# AWG_EEM_Connectors_JTAG.net
KiCad netlist of a schematic drawn in Altium Designer
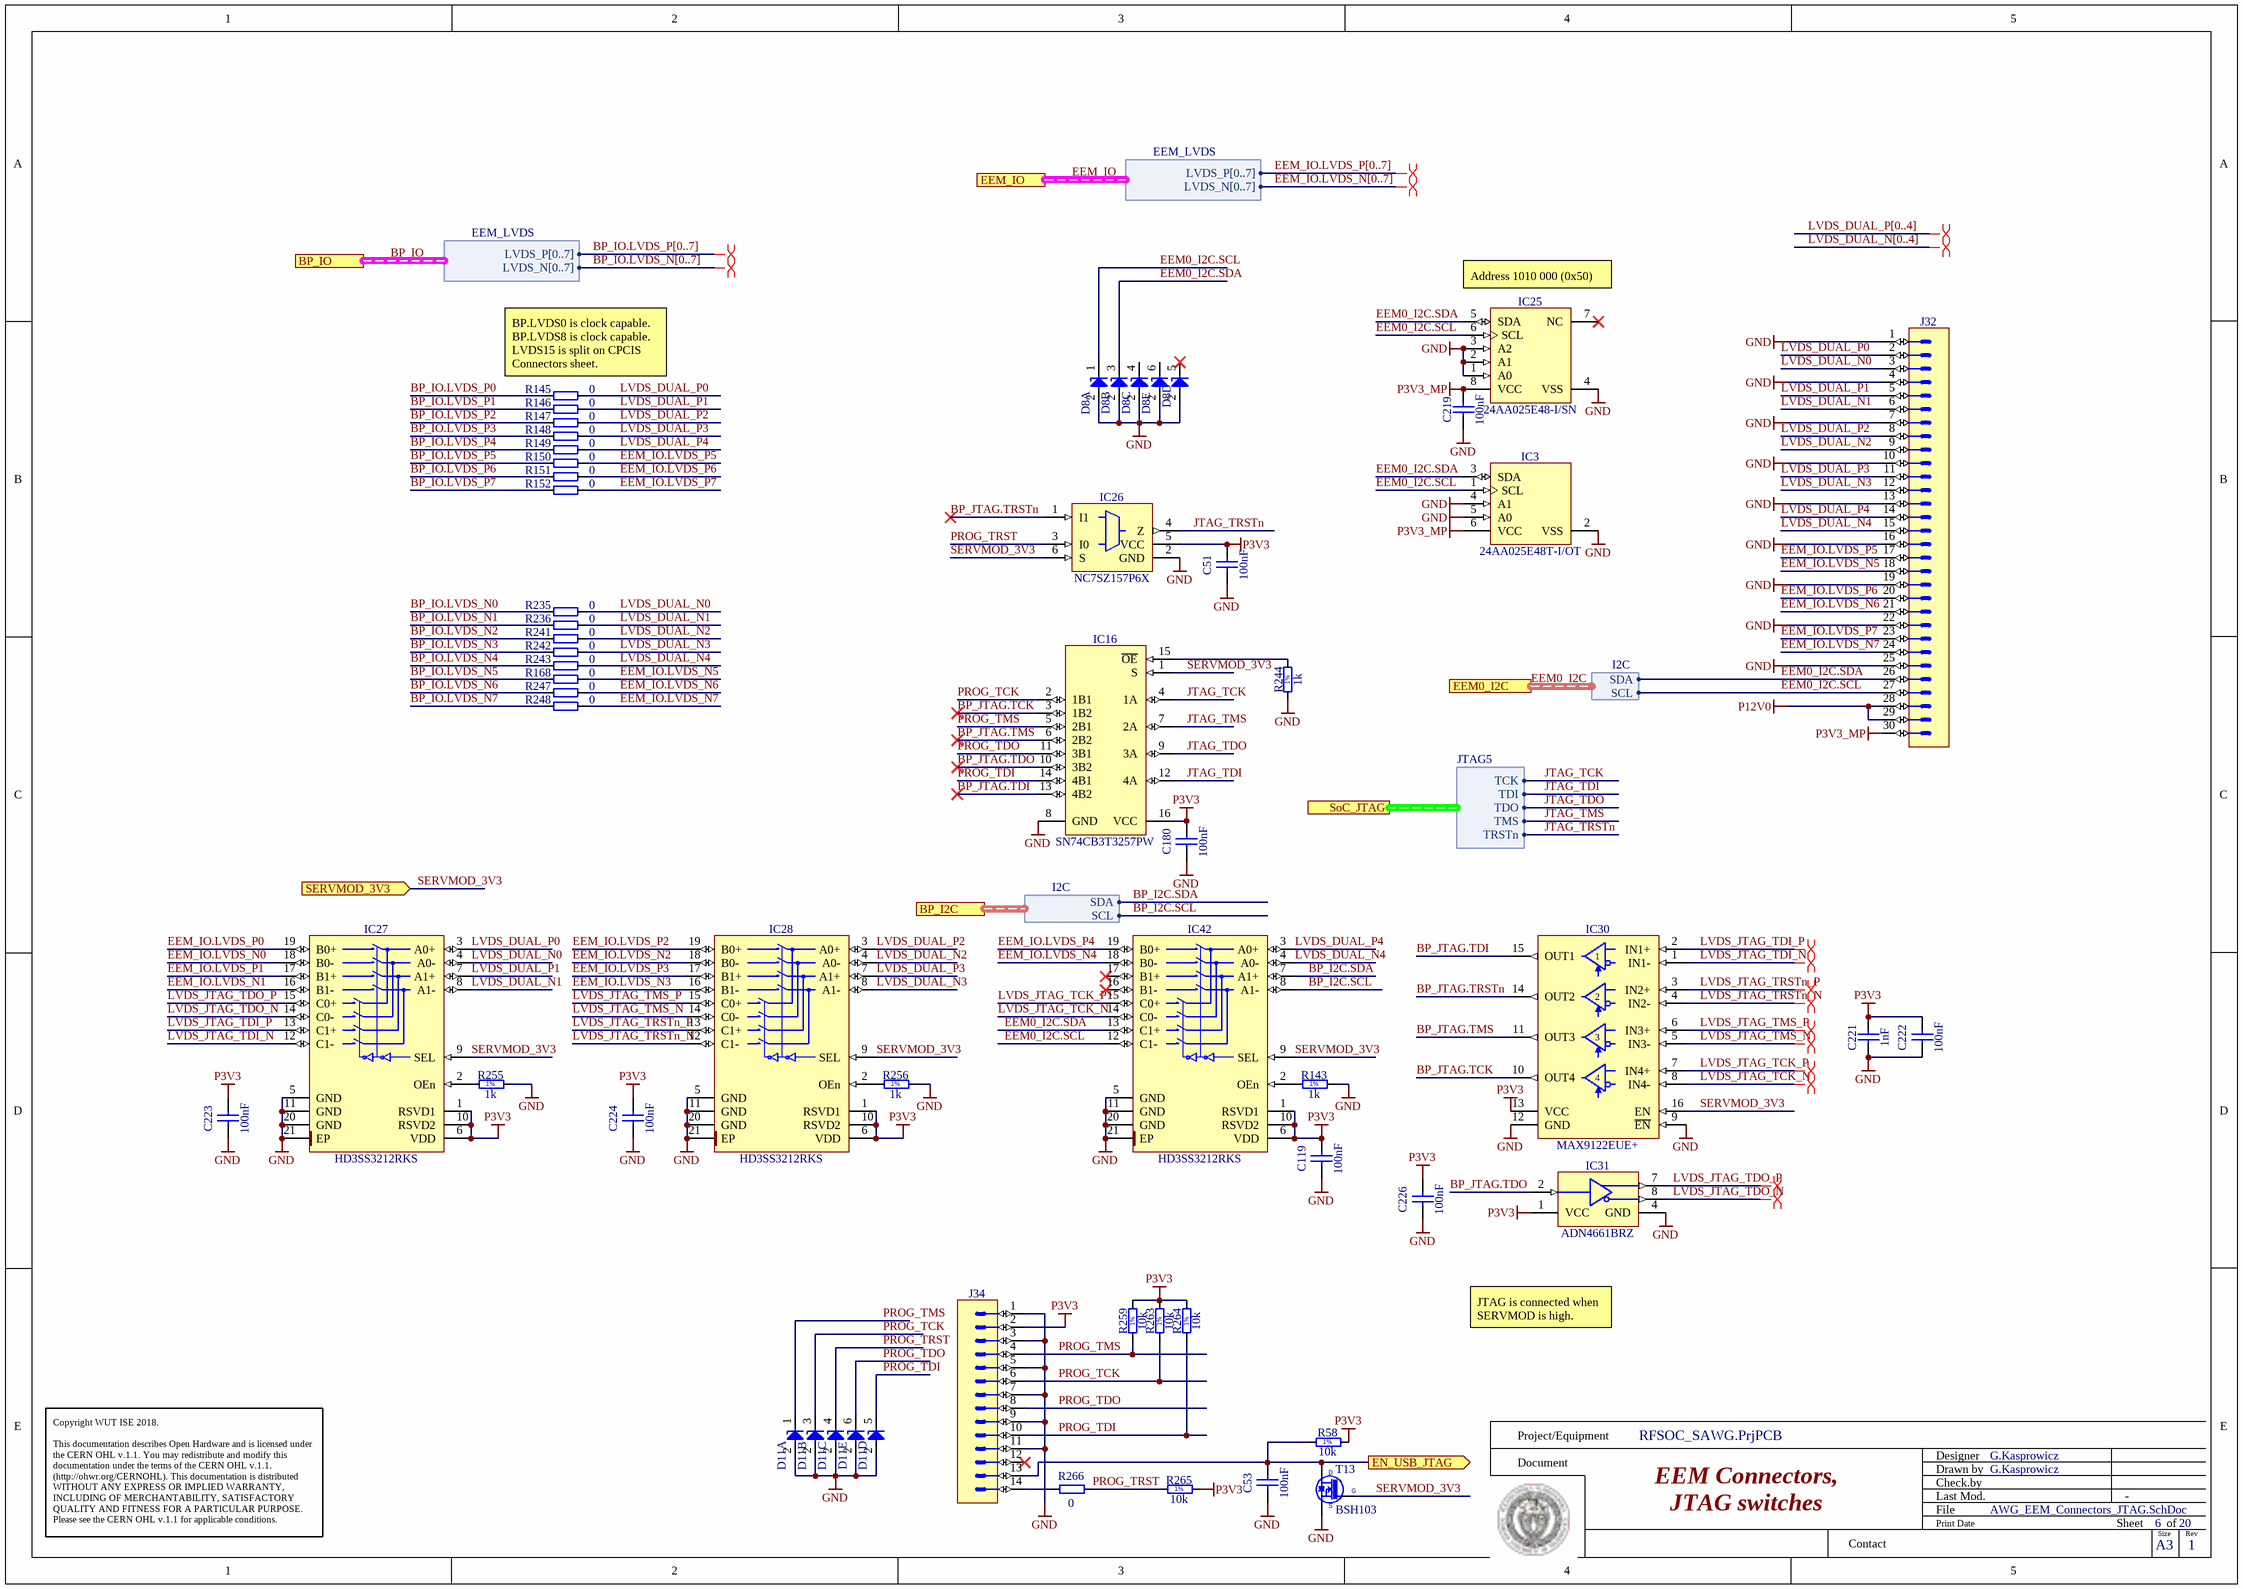
[diagram p0: AWG_EEM_Connectors_JTAG.SchDoc]

(export (version "E")
  (design (tool "Eeschema 10.0.6"))
  (components
    (comp (ref "C51")
      (value "100nF")
      (footprint "CAPC1005X55N")
      (description "Non-polarised capacitor")
      (fields
        (field (name "PART NUMBER") "CC0402_100NF_25V_10%_X7R_YUDEN_TMK105B7104KVHF")
        (field (name "VOLTAGE") "25V")
        (field (name "AUTHOR") "CERN DEM JLC")
      )
      (libsource (lib "Capacitors") (part "Capacitor - non polarized"))
    )
    (comp (ref "C53")
      (value "100nF")
      (footprint "CAPC1005X55N")
      (description "Non-polarised capacitor")
      (fields
        (field (name "PART NUMBER") "CC0402_100NF_25V_10%_X7R_YUDEN_TMK105B7104KVHF")
        (field (name "VOLTAGE") "25V")
        (field (name "AUTHOR") "CERN DEM JLC")
      )
      (libsource (lib "Capacitors") (part "Capacitor - non polarized"))
    )
    (comp (ref "C119")
      (value "100nF")
      (footprint "CAPC1005X55N")
      (description "Non-polarised capacitor")
      (fields
        (field (name "PART NUMBER") "CC0402_100NF_25V_10%_X7R_YUDEN_TMK105B7104KVHF")
        (field (name "VOLTAGE") "25V")
        (field (name "AUTHOR") "CERN DEM JLC")
      )
      (libsource (lib "Capacitors") (part "Capacitor - non polarized"))
    )
    (comp (ref "C180")
      (value "100nF")
      (footprint "CAPC1005X55N")
      (description "Non-polarised capacitor")
      (fields
        (field (name "PART NUMBER") "CC0402_100NF_25V_10%_X7R_YUDEN_TMK105B7104KVHF")
        (field (name "VOLTAGE") "25V")
        (field (name "AUTHOR") "CERN DEM JLC")
      )
      (libsource (lib "Capacitors") (part "Capacitor - non polarized"))
    )
    (comp (ref "C219")
      (value "100nF")
      (footprint "CAPC1005X55N")
      (description "Non-polarised capacitor")
      (fields
        (field (name "PART NUMBER") "CC0402_100NF_25V_10%_X7R_YUDEN_TMK105B7104KVHF")
        (field (name "VOLTAGE") "25V")
        (field (name "AUTHOR") "CERN DEM JLC")
      )
      (libsource (lib "Capacitors") (part "Capacitor - non polarized"))
    )
    (comp (ref "C221")
      (value "1nF")
      (footprint "CAPC1005X55N")
      (description "Non-polarised capacitor")
      (fields
        (field (name "MANUFACTURER PART NUMBER") "CC0402_1NF_50V_10%_X7R")
        (field (name "MANUFACTURER") "GENERIC")
        (field (name "AUTHOR") "CERN DEM JLC")
      )
      (libsource (lib "Capacitors") (part "Capacitor - non polarized"))
    )
    (comp (ref "C222")
      (value "100nF")
      (footprint "CAPC1005X55N")
      (description "Non-polarised capacitor")
      (fields
        (field (name "PART NUMBER") "CC0402_100NF_25V_10%_X7R_YUDEN_TMK105B7104KVHF")
        (field (name "VOLTAGE") "25V")
        (field (name "AUTHOR") "CERN DEM JLC")
      )
      (libsource (lib "Capacitors") (part "Capacitor - non polarized"))
    )
    (comp (ref "C223")
      (value "100nF")
      (footprint "CAPC1005X55N")
      (description "Non-polarised capacitor")
      (fields
        (field (name "PART NUMBER") "CC0402_100NF_25V_10%_X7R_YUDEN_TMK105B7104KVHF")
        (field (name "VOLTAGE") "25V")
        (field (name "AUTHOR") "CERN DEM JLC")
      )
      (libsource (lib "Capacitors") (part "Capacitor - non polarized"))
    )
    (comp (ref "C224")
      (value "100nF")
      (footprint "CAPC1005X55N")
      (description "Non-polarised capacitor")
      (fields
        (field (name "PART NUMBER") "CC0402_100NF_25V_10%_X7R_YUDEN_TMK105B7104KVHF")
        (field (name "VOLTAGE") "25V")
        (field (name "AUTHOR") "CERN DEM JLC")
      )
      (libsource (lib "Capacitors") (part "Capacitor - non polarized"))
    )
    (comp (ref "C226")
      (value "100nF")
      (footprint "CAPC1005X55N")
      (description "Non-polarised capacitor")
      (fields
        (field (name "PART NUMBER") "CC0402_100NF_25V_10%_X7R_YUDEN_TMK105B7104KVHF")
        (field (name "VOLTAGE") "25V")
        (field (name "AUTHOR") "CERN DEM JLC")
      )
      (libsource (lib "Capacitors") (part "Capacitor - non polarized"))
    )
    (comp (ref "D8")
      (value "PESD3V3L5UY")
      (footprint "SOT65P210X110-6N")
      (description "Fivefold ESD Protection Diode Arrays")
      (fields
        (field (name "VOLTAGE") "3.3V")
        (field (name "POWER") "200W")
        (field (name "AUTHOR") "CERN DEM WB")
      )
      (libsource (lib "ICs And Semiconductors") (part "PESD Array 5diodes 6pins Common anode2"))
    )
    (comp (ref "D11")
      (value "PESD3V3L5UY")
      (footprint "SOT65P210X110-6N")
      (description "Fivefold ESD Protection Diode Arrays")
      (fields
        (field (name "VOLTAGE") "3.3V")
        (field (name "POWER") "200W")
        (field (name "AUTHOR") "CERN DEM WB")
      )
      (libsource (lib "ICs And Semiconductors") (part "PESD Array 5diodes 6pins Common anode2"))
    )
    (comp (ref "IC3")
      (value "24AA025E48T-I/OT")
      (footprint "SOT95P280X145-6N")
      (description "1.7V-5.5V, 2K I2C Serial EEPROM With EUI-48 Node Identity")
      (fields (field (name "MANUFACTURER") "MICROCHIP TECHNOLOGY") (field (name "AUTHOR") "CERN DEM BC"))
      (libsource (lib "ICs And Semiconductors") (part "24AA025E48T-I/OT"))
    )
    (comp (ref "IC16")
      (value "SN74CB3T3257PW")
      (footprint "SOP65P640X120-16N")
      (description "4-BIT 1-OF-2 FET Multiplexer/Demultiplexer 2.5V/3.3V Low-Voltage Bus Switch 5V Tolerant Shifter")
      (fields (field (name "MANUFACTURER") "TEXAS INSTRUMENTS") (field (name "AUTHOR") "CERN DEM JLC"))
      (libsource (lib "ICs And Semiconductors") (part "743257"))
    )
    (comp (ref "IC25")
      (value "24AA025E48-I/SN")
      (footprint "SOIC127P600X175-8N")
      (description "1.7V-5.5V, 2K I2C™ Serial EEPROMs with EUI-48™ Node Identity")
      (fields (field (name "MANUFACTURER") "MICROCHIP TECHNOLOGY") (field (name "AUTHOR") "CERN DEM MR"))
      (libsource (lib "ICs And Semiconductors") (part "24AA025E48-I/SN"))
    )
    (comp (ref "IC26")
      (value "NC7SZ157P6X")
      (footprint "SOT65P210X110-6N")
      (description "TinyLogic® UHS 2-Input Non-Inverting Multiplexer")
      (fields (field (name "MANUFACTURER") "FAIRCHILD SEMICONDUCTOR") (field (name "AUTHOR") "CERN DEM JLC"))
      (libsource (lib "ICs And Semiconductors") (part "NC7SZ157"))
    )
    (comp (ref "IC27")
      (value "HD3SS3212RKS")
      (footprint "TEXAS_RKS0020A")
      (description "Two-Channel Differential 2:1/1:2 USB3.1 Mux/Demux")
      (fields (field (name "MANUFACTURER") "TEXAS INSTRUMENTS") (field (name "AUTHOR") "CERN DEM BC"))
      (libsource (lib "ICs And Semiconductors") (part "HD3SS3212RKS"))
    )
    (comp (ref "IC28")
      (value "HD3SS3212RKS")
      (footprint "TEXAS_RKS0020A")
      (description "Two-Channel Differential 2:1/1:2 USB3.1 Mux/Demux")
      (fields (field (name "MANUFACTURER") "TEXAS INSTRUMENTS") (field (name "AUTHOR") "CERN DEM BC"))
      (libsource (lib "ICs And Semiconductors") (part "HD3SS3212RKS"))
    )
    (comp (ref "IC30")
      (value "MAX9122EUE+")
      (footprint "SOP65P640X110-16N")
      (description "Quad LVDS Line Receivers with Integrated Termination and Flow-Through Pinout")
      (fields (field (name "MANUFACTURER") "MAXIM") (field (name "AUTHOR") "CERN DEM MR"))
      (libsource (lib "ICs And Semiconductors") (part "MAX9122"))
    )
    (comp (ref "IC31")
      (value "ADN4661BRZ")
      (footprint "SOIC127P600X175-8N")
      (description "Single, 3V, CMOS, LVDS, High Speed Differential Driver")
      (fields (field (name "MANUFACTURER") "ANALOG DEVICES") (field (name "AUTHOR") "CERN DEM JMW"))
      (libsource (lib "ICs And Semiconductors") (part "ADN4661"))
    )
    (comp (ref "IC42")
      (value "HD3SS3212RKS")
      (footprint "TEXAS_RKS0020A")
      (description "Two-Channel Differential 2:1/1:2 USB3.1 Mux/Demux")
      (fields (field (name "MANUFACTURER") "TEXAS INSTRUMENTS") (field (name "AUTHOR") "CERN DEM BC"))
      (libsource (lib "ICs And Semiconductors") (part "HD3SS3212RKS"))
    )
    (comp (ref "J32")
      (value "~")
      (footprint "3M_N2530-6002RB")
      (description "Connector 30 Male")
      (fields
        (field (name "PART NUMBER") "3M_N2530-6002RB")
        (field (name "MANUFACTURER") "3M")
        (field (name "AUTHOR") "CERN DEM JLC")
      )
      (libsource (lib "Connectors") (part "Connector 30 Male"))
    )
    (comp (ref "J34")
      (value "Milli-Grid™")
      (footprint "MOLEX_87832-1420")
      (description "Connector 14 Male")
      (fields
        (field (name "PART NUMBER") "MOLEX_87832-1420")
        (field (name "MANUFACTURER") "MOLEX")
        (field (name "AUTHOR") "CERN DEM JLC")
      )
      (libsource (lib "Connectors") (part "Connector 14 Male"))
    )
    (comp (ref "R58")
      (value "10k")
      (footprint "RESC1005X40N")
      (description "Resistor - 1%")
      (fields
        (field (name "PART NUMBER") "R0402_10K_1%_0.0625W_100PPM")
        (field (name "POWER") "0.0625W")
        (field (name "AUTHOR") "CERN DEM JLC")
      )
      (libsource (lib "Resistors") (part "Resistor - 1%"))
    )
    (comp (ref "R143")
      (value "1k")
      (footprint "RESC1005X40N")
      (description "Resistor - 1%")
      (fields
        (field (name "PART NUMBER") "R0402_1K_1%_0.0625W_100PPM")
        (field (name "POWER") "0.0625W")
        (field (name "AUTHOR") "CERN DEM JLC")
      )
      (libsource (lib "Resistors") (part "Resistor - 1%"))
    )
    (comp (ref "R145")
      (value "0")
      (footprint "RESC1005X40N")
      (description "Resistor")
      (fields
        (field (name "PART NUMBER") "R0402_0R_JUMPER")
        (field (name "MANUFACTURER") "GENERIC")
        (field (name "AUTHOR") "CERN DEM JLC")
      )
      (libsource (lib "Resistors") (part "Resistor"))
    )
    (comp (ref "R146")
      (value "0")
      (footprint "RESC1005X40N")
      (description "Resistor")
      (fields
        (field (name "PART NUMBER") "R0402_0R_JUMPER")
        (field (name "MANUFACTURER") "GENERIC")
        (field (name "AUTHOR") "CERN DEM JLC")
      )
      (libsource (lib "Resistors") (part "Resistor"))
    )
    (comp (ref "R147")
      (value "0")
      (footprint "RESC1005X40N")
      (description "Resistor")
      (fields
        (field (name "PART NUMBER") "R0402_0R_JUMPER")
        (field (name "MANUFACTURER") "GENERIC")
        (field (name "AUTHOR") "CERN DEM JLC")
      )
      (libsource (lib "Resistors") (part "Resistor"))
    )
    (comp (ref "R148")
      (value "0")
      (footprint "RESC1005X40N")
      (description "Resistor")
      (fields
        (field (name "PART NUMBER") "R0402_0R_JUMPER")
        (field (name "MANUFACTURER") "GENERIC")
        (field (name "AUTHOR") "CERN DEM JLC")
      )
      (libsource (lib "Resistors") (part "Resistor"))
    )
    (comp (ref "R149")
      (value "0")
      (footprint "RESC1005X40N")
      (description "Resistor")
      (fields
        (field (name "PART NUMBER") "R0402_0R_JUMPER")
        (field (name "MANUFACTURER") "GENERIC")
        (field (name "AUTHOR") "CERN DEM JLC")
      )
      (libsource (lib "Resistors") (part "Resistor"))
    )
    (comp (ref "R150")
      (value "0")
      (footprint "RESC1005X40N")
      (description "Resistor")
      (fields
        (field (name "PART NUMBER") "R0402_0R_JUMPER")
        (field (name "MANUFACTURER") "GENERIC")
        (field (name "AUTHOR") "CERN DEM JLC")
      )
      (libsource (lib "Resistors") (part "Resistor"))
    )
    (comp (ref "R151")
      (value "0")
      (footprint "RESC1005X40N")
      (description "Resistor")
      (fields
        (field (name "PART NUMBER") "R0402_0R_JUMPER")
        (field (name "MANUFACTURER") "GENERIC")
        (field (name "AUTHOR") "CERN DEM JLC")
      )
      (libsource (lib "Resistors") (part "Resistor"))
    )
    (comp (ref "R152")
      (value "0")
      (footprint "RESC1005X40N")
      (description "Resistor")
      (fields
        (field (name "PART NUMBER") "R0402_0R_JUMPER")
        (field (name "MANUFACTURER") "GENERIC")
        (field (name "AUTHOR") "CERN DEM JLC")
      )
      (libsource (lib "Resistors") (part "Resistor"))
    )
    (comp (ref "R168")
      (value "0")
      (footprint "RESC1005X40N")
      (description "Resistor")
      (fields
        (field (name "PART NUMBER") "R0402_0R_JUMPER")
        (field (name "MANUFACTURER") "GENERIC")
        (field (name "AUTHOR") "CERN DEM JLC")
      )
      (libsource (lib "Resistors") (part "Resistor"))
    )
    (comp (ref "R235")
      (value "0")
      (footprint "RESC1005X40N")
      (description "Resistor")
      (fields
        (field (name "PART NUMBER") "R0402_0R_JUMPER")
        (field (name "MANUFACTURER") "GENERIC")
        (field (name "AUTHOR") "CERN DEM JLC")
      )
      (libsource (lib "Resistors") (part "Resistor"))
    )
    (comp (ref "R236")
      (value "0")
      (footprint "RESC1005X40N")
      (description "Resistor")
      (fields
        (field (name "PART NUMBER") "R0402_0R_JUMPER")
        (field (name "MANUFACTURER") "GENERIC")
        (field (name "AUTHOR") "CERN DEM JLC")
      )
      (libsource (lib "Resistors") (part "Resistor"))
    )
    (comp (ref "R241")
      (value "0")
      (footprint "RESC1005X40N")
      (description "Resistor")
      (fields
        (field (name "PART NUMBER") "R0402_0R_JUMPER")
        (field (name "MANUFACTURER") "GENERIC")
        (field (name "AUTHOR") "CERN DEM JLC")
      )
      (libsource (lib "Resistors") (part "Resistor"))
    )
    (comp (ref "R242")
      (value "0")
      (footprint "RESC1005X40N")
      (description "Resistor")
      (fields
        (field (name "PART NUMBER") "R0402_0R_JUMPER")
        (field (name "MANUFACTURER") "GENERIC")
        (field (name "AUTHOR") "CERN DEM JLC")
      )
      (libsource (lib "Resistors") (part "Resistor"))
    )
    (comp (ref "R243")
      (value "0")
      (footprint "RESC1005X40N")
      (description "Resistor")
      (fields
        (field (name "PART NUMBER") "R0402_0R_JUMPER")
        (field (name "MANUFACTURER") "GENERIC")
        (field (name "AUTHOR") "CERN DEM JLC")
      )
      (libsource (lib "Resistors") (part "Resistor"))
    )
    (comp (ref "R244")
      (value "1k")
      (footprint "RESC1005X40N")
      (description "Resistor - 1%")
      (fields
        (field (name "PART NUMBER") "R0402_1K_1%_0.0625W_100PPM")
        (field (name "POWER") "0.0625W")
        (field (name "AUTHOR") "CERN DEM JLC")
      )
      (libsource (lib "Resistors") (part "Resistor - 1%"))
    )
    (comp (ref "R247")
      (value "0")
      (footprint "RESC1005X40N")
      (description "Resistor")
      (fields
        (field (name "PART NUMBER") "R0402_0R_JUMPER")
        (field (name "MANUFACTURER") "GENERIC")
        (field (name "AUTHOR") "CERN DEM JLC")
      )
      (libsource (lib "Resistors") (part "Resistor"))
    )
    (comp (ref "R248")
      (value "0")
      (footprint "RESC1005X40N")
      (description "Resistor")
      (fields
        (field (name "PART NUMBER") "R0402_0R_JUMPER")
        (field (name "MANUFACTURER") "GENERIC")
        (field (name "AUTHOR") "CERN DEM JLC")
      )
      (libsource (lib "Resistors") (part "Resistor"))
    )
    (comp (ref "R255")
      (value "1k")
      (footprint "RESC1005X40N")
      (description "Resistor - 1%")
      (fields
        (field (name "PART NUMBER") "R0402_1K_1%_0.0625W_100PPM")
        (field (name "POWER") "0.0625W")
        (field (name "AUTHOR") "CERN DEM JLC")
      )
      (libsource (lib "Resistors") (part "Resistor - 1%"))
    )
    (comp (ref "R256")
      (value "1k")
      (footprint "RESC1005X40N")
      (description "Resistor - 1%")
      (fields
        (field (name "PART NUMBER") "R0402_1K_1%_0.0625W_100PPM")
        (field (name "POWER") "0.0625W")
        (field (name "AUTHOR") "CERN DEM JLC")
      )
      (libsource (lib "Resistors") (part "Resistor - 1%"))
    )
    (comp (ref "R259")
      (value "10k")
      (footprint "RESC1005X40N")
      (description "Resistor - 1%")
      (fields
        (field (name "PART NUMBER") "R0402_10K_1%_0.0625W_100PPM")
        (field (name "POWER") "0.0625W")
        (field (name "AUTHOR") "CERN DEM JLC")
      )
      (libsource (lib "Resistors") (part "Resistor - 1%"))
    )
    (comp (ref "R263")
      (value "10k")
      (footprint "RESC1005X40N")
      (description "Resistor - 1%")
      (fields
        (field (name "PART NUMBER") "R0402_10K_1%_0.0625W_100PPM")
        (field (name "POWER") "0.0625W")
        (field (name "AUTHOR") "CERN DEM JLC")
      )
      (libsource (lib "Resistors") (part "Resistor - 1%"))
    )
    (comp (ref "R264")
      (value "10k")
      (footprint "RESC1005X40N")
      (description "Resistor - 1%")
      (fields
        (field (name "PART NUMBER") "R0402_10K_1%_0.0625W_100PPM")
        (field (name "POWER") "0.0625W")
        (field (name "AUTHOR") "CERN DEM JLC")
      )
      (libsource (lib "Resistors") (part "Resistor - 1%"))
    )
    (comp (ref "R265")
      (value "10k")
      (footprint "RESC1005X40N")
      (description "Resistor - 1%")
      (fields
        (field (name "PART NUMBER") "R0402_10K_1%_0.0625W_100PPM")
        (field (name "POWER") "0.0625W")
        (field (name "AUTHOR") "CERN DEM JLC")
      )
      (libsource (lib "Resistors") (part "Resistor - 1%"))
    )
    (comp (ref "R266")
      (value "0")
      (footprint "RESC1005X40N")
      (description "Resistor")
      (fields
        (field (name "MANUFACTURER PART NUMBER") "R0402_0R_JUMPER")
        (field (name "MANUFACTURER") "GENERIC")
        (field (name "AUTHOR") "CERN DEM JLC")
      )
      (libsource (lib "Resistors") (part "Resistor"))
    )
    (comp (ref "T13")
      (value "BSH103")
      (footprint "SOT95P230X110-3N")
      (description "N-CHANNEL MOSFET WITH DIODE")
      (fields (field (name "MANUFACTURER") "NEXPERIA") (field (name "AUTHOR") "CERN DEM JLC"))
      (libsource (lib "ICs And Semiconductors") (part "N-MOSFET-D 1G 2S 3D"))
    )
  )
  (nets
    (net (code "6") (name "/BP_I2C.SCL") (class "Default")
      (node (ref "IC42") (pin "8") (pinfunction "A1-_8") (pintype "bidirectional"))
    )
    (net (code "7") (name "/BP_I2C.SDA") (class "Default")
      (node (ref "IC42") (pin "7") (pinfunction "A1+_7") (pintype "bidirectional"))
    )
    (net (code "8") (name "/BP_IO.LVDS_N0") (class "Default")
      (node (ref "R235") (pin "1") (pinfunction "1_1") (pintype "passive"))
    )
    (net (code "9") (name "/BP_IO.LVDS_N1") (class "Default")
      (node (ref "R236") (pin "1") (pinfunction "1_1") (pintype "passive"))
    )
    (net (code "10") (name "/BP_IO.LVDS_N2") (class "Default")
      (node (ref "R241") (pin "1") (pinfunction "1_1") (pintype "passive"))
    )
    (net (code "11") (name "/BP_IO.LVDS_N3") (class "Default")
      (node (ref "R242") (pin "1") (pinfunction "1_1") (pintype "passive"))
    )
    (net (code "12") (name "/BP_IO.LVDS_N4") (class "Default")
      (node (ref "R243") (pin "1") (pinfunction "1_1") (pintype "passive"))
    )
    (net (code "13") (name "/BP_IO.LVDS_N5") (class "Default")
      (node (ref "R168") (pin "1") (pinfunction "1_1") (pintype "passive"))
    )
    (net (code "14") (name "/BP_IO.LVDS_N6") (class "Default")
      (node (ref "R247") (pin "1") (pinfunction "1_1") (pintype "passive"))
    )
    (net (code "15") (name "/BP_IO.LVDS_N7") (class "Default")
      (node (ref "R248") (pin "1") (pinfunction "1_1") (pintype "passive"))
    )
    (net (code "16") (name "/BP_IO.LVDS_P0") (class "Default")
      (node (ref "R145") (pin "1") (pinfunction "1_1") (pintype "passive"))
    )
    (net (code "17") (name "/BP_IO.LVDS_P1") (class "Default")
      (node (ref "R146") (pin "1") (pinfunction "1_1") (pintype "passive"))
    )
    (net (code "18") (name "/BP_IO.LVDS_P2") (class "Default")
      (node (ref "R147") (pin "1") (pinfunction "1_1") (pintype "passive"))
    )
    (net (code "19") (name "/BP_IO.LVDS_P3") (class "Default")
      (node (ref "R148") (pin "1") (pinfunction "1_1") (pintype "passive"))
    )
    (net (code "20") (name "/BP_IO.LVDS_P4") (class "Default")
      (node (ref "R149") (pin "1") (pinfunction "1_1") (pintype "passive"))
    )
    (net (code "21") (name "/BP_IO.LVDS_P5") (class "Default")
      (node (ref "R150") (pin "1") (pinfunction "1_1") (pintype "passive"))
    )
    (net (code "22") (name "/BP_IO.LVDS_P6") (class "Default")
      (node (ref "R151") (pin "1") (pinfunction "1_1") (pintype "passive"))
    )
    (net (code "23") (name "/BP_IO.LVDS_P7") (class "Default")
      (node (ref "R152") (pin "1") (pinfunction "1_1") (pintype "passive"))
    )
    (net (code "25") (name "/BP_JTAG.TCK") (class "Default")
      (node (ref "IC16") (pin "3") (pinfunction "1B2_3") (pintype "bidirectional"))
      (node (ref "IC30") (pin "10") (pinfunction "OUT4_10") (pintype "output"))
    )
    (net (code "26") (name "/BP_JTAG.TDI") (class "Default")
      (node (ref "IC16") (pin "13") (pinfunction "4B2_13") (pintype "bidirectional"))
      (node (ref "IC30") (pin "15") (pinfunction "OUT1_15") (pintype "output"))
    )
    (net (code "27") (name "/BP_JTAG.TDO") (class "Default")
      (node (ref "IC16") (pin "10") (pinfunction "3B2_10") (pintype "bidirectional"))
      (node (ref "IC31") (pin "2") (pinfunction "DIN_2") (pintype "input"))
    )
    (net (code "28") (name "/BP_JTAG.TMS") (class "Default")
      (node (ref "IC16") (pin "6") (pinfunction "2B2_6") (pintype "bidirectional"))
      (node (ref "IC30") (pin "11") (pinfunction "OUT3_11") (pintype "output"))
    )
    (net (code "29") (name "/BP_JTAG.TRSTn") (class "Default")
      (node (ref "IC26") (pin "1") (pinfunction "I1_1") (pintype "input"))
      (node (ref "IC30") (pin "14") (pinfunction "OUT2_14") (pintype "output"))
    )
    (net (code "30") (name "/EEM0_I2C.SCL") (class "Default")
      (node (ref "D8") (pin "1") (pinfunction "C_1") (pintype "passive"))
      (node (ref "IC25") (pin "6") (pinfunction "SCL_6") (pintype "input"))
      (node (ref "IC3") (pin "1") (pinfunction "SCL_1") (pintype "input"))
      (node (ref "IC42") (pin "12") (pinfunction "C1-_12") (pintype "bidirectional"))
      (node (ref "J32") (pin "27") (pinfunction "27_27") (pintype "bidirectional"))
    )
    (net (code "31") (name "/EEM0_I2C.SDA") (class "Default")
      (node (ref "D8") (pin "3") (pinfunction "C_3") (pintype "passive"))
      (node (ref "IC25") (pin "5") (pinfunction "SDA_5") (pintype "bidirectional"))
      (node (ref "IC3") (pin "3") (pinfunction "SDA_3") (pintype "bidirectional"))
      (node (ref "IC42") (pin "13") (pinfunction "C1+_13") (pintype "bidirectional"))
      (node (ref "J32") (pin "26") (pinfunction "26_26") (pintype "bidirectional"))
    )
    (net (code "33") (name "/EEM_IO.LVDS_N0") (class "Default")
      (node (ref "IC27") (pin "18") (pinfunction "B0-_18") (pintype "bidirectional"))
    )
    (net (code "34") (name "/EEM_IO.LVDS_N1") (class "Default")
      (node (ref "IC27") (pin "16") (pinfunction "B1-_16") (pintype "bidirectional"))
    )
    (net (code "35") (name "/EEM_IO.LVDS_N2") (class "Default")
      (node (ref "IC28") (pin "18") (pinfunction "B0-_18") (pintype "bidirectional"))
    )
    (net (code "36") (name "/EEM_IO.LVDS_N3") (class "Default")
      (node (ref "IC28") (pin "16") (pinfunction "B1-_16") (pintype "bidirectional"))
    )
    (net (code "37") (name "/EEM_IO.LVDS_N4") (class "Default")
      (node (ref "IC42") (pin "18") (pinfunction "B0-_18") (pintype "bidirectional"))
    )
    (net (code "38") (name "/EEM_IO.LVDS_N5") (class "Default")
      (node (ref "J32") (pin "18") (pinfunction "18_18") (pintype "bidirectional"))
      (node (ref "R168") (pin "2") (pinfunction "2_2") (pintype "passive"))
    )
    (net (code "39") (name "/EEM_IO.LVDS_N6") (class "Default")
      (node (ref "J32") (pin "21") (pinfunction "21_21") (pintype "bidirectional"))
      (node (ref "R247") (pin "2") (pinfunction "2_2") (pintype "passive"))
    )
    (net (code "40") (name "/EEM_IO.LVDS_N7") (class "Default")
      (node (ref "J32") (pin "24") (pinfunction "24_24") (pintype "bidirectional"))
      (node (ref "R248") (pin "2") (pinfunction "2_2") (pintype "passive"))
    )
    (net (code "42") (name "/EEM_IO.LVDS_P0") (class "Default")
      (node (ref "IC27") (pin "19") (pinfunction "B0+_19") (pintype "bidirectional"))
    )
    (net (code "43") (name "/EEM_IO.LVDS_P1") (class "Default")
      (node (ref "IC27") (pin "17") (pinfunction "B1+_17") (pintype "bidirectional"))
    )
    (net (code "44") (name "/EEM_IO.LVDS_P2") (class "Default")
      (node (ref "IC28") (pin "19") (pinfunction "B0+_19") (pintype "bidirectional"))
    )
    (net (code "45") (name "/EEM_IO.LVDS_P3") (class "Default")
      (node (ref "IC28") (pin "17") (pinfunction "B1+_17") (pintype "bidirectional"))
    )
    (net (code "46") (name "/EEM_IO.LVDS_P4") (class "Default")
      (node (ref "IC42") (pin "19") (pinfunction "B0+_19") (pintype "bidirectional"))
    )
    (net (code "47") (name "/EEM_IO.LVDS_P5") (class "Default")
      (node (ref "J32") (pin "17") (pinfunction "17_17") (pintype "bidirectional"))
      (node (ref "R150") (pin "2") (pinfunction "2_2") (pintype "passive"))
    )
    (net (code "48") (name "/EEM_IO.LVDS_P6") (class "Default")
      (node (ref "J32") (pin "20") (pinfunction "20_20") (pintype "bidirectional"))
      (node (ref "R151") (pin "2") (pinfunction "2_2") (pintype "passive"))
    )
    (net (code "49") (name "/EEM_IO.LVDS_P7") (class "Default")
      (node (ref "J32") (pin "23") (pinfunction "23_23") (pintype "bidirectional"))
      (node (ref "R152") (pin "2") (pinfunction "2_2") (pintype "passive"))
    )
    (net (code "50") (name "/EN_USB_JTAG") (class "Default")
      (node (ref "C53") (pin "2") (pinfunction "2_2") (pintype "passive"))
      (node (ref "J34") (pin "13") (pinfunction "13_13") (pintype "bidirectional"))
      (node (ref "R58") (pin "1") (pinfunction "1_1") (pintype "passive"))
      (node (ref "T13") (pin "3") (pinfunction "D_3") (pintype "passive"))
    )
    (net (code "51") (name "/JTAG_TCK") (class "Default")
      (node (ref "IC16") (pin "4") (pinfunction "1A_4") (pintype "bidirectional"))
    )
    (net (code "52") (name "/JTAG_TDI") (class "Default")
      (node (ref "IC16") (pin "12") (pinfunction "4A_12") (pintype "bidirectional"))
    )
    (net (code "53") (name "/JTAG_TDO") (class "Default")
      (node (ref "IC16") (pin "9") (pinfunction "3A_9") (pintype "bidirectional"))
    )
    (net (code "54") (name "/JTAG_TMS") (class "Default")
      (node (ref "IC16") (pin "7") (pinfunction "2A_7") (pintype "bidirectional"))
    )
    (net (code "55") (name "/JTAG_TRSTn") (class "Default")
      (node (ref "IC26") (pin "4") (pinfunction "Z_4") (pintype "output"))
    )
    (net (code "56") (name "/LVDS_DUAL_N0") (class "Default")
      (node (ref "IC27") (pin "4") (pinfunction "A0-_4") (pintype "bidirectional"))
      (node (ref "J32") (pin "3") (pinfunction "3_3") (pintype "bidirectional"))
      (node (ref "R235") (pin "2") (pinfunction "2_2") (pintype "passive"))
    )
    (net (code "57") (name "/LVDS_DUAL_N1") (class "Default")
      (node (ref "IC27") (pin "8") (pinfunction "A1-_8") (pintype "bidirectional"))
      (node (ref "J32") (pin "6") (pinfunction "6_6") (pintype "bidirectional"))
      (node (ref "R236") (pin "2") (pinfunction "2_2") (pintype "passive"))
    )
    (net (code "58") (name "/LVDS_DUAL_N2") (class "Default")
      (node (ref "IC28") (pin "4") (pinfunction "A0-_4") (pintype "bidirectional"))
      (node (ref "J32") (pin "9") (pinfunction "9_9") (pintype "bidirectional"))
      (node (ref "R241") (pin "2") (pinfunction "2_2") (pintype "passive"))
    )
    (net (code "59") (name "/LVDS_DUAL_N3") (class "Default")
      (node (ref "IC28") (pin "8") (pinfunction "A1-_8") (pintype "bidirectional"))
      (node (ref "J32") (pin "12") (pinfunction "12_12") (pintype "bidirectional"))
      (node (ref "R242") (pin "2") (pinfunction "2_2") (pintype "passive"))
    )
    (net (code "60") (name "/LVDS_DUAL_N4") (class "Default")
      (node (ref "IC42") (pin "4") (pinfunction "A0-_4") (pintype "bidirectional"))
      (node (ref "J32") (pin "15") (pinfunction "15_15") (pintype "bidirectional"))
      (node (ref "R243") (pin "2") (pinfunction "2_2") (pintype "passive"))
    )
    (net (code "62") (name "/LVDS_DUAL_P0") (class "Default")
      (node (ref "IC27") (pin "3") (pinfunction "A0+_3") (pintype "bidirectional"))
      (node (ref "J32") (pin "2") (pinfunction "2_2") (pintype "bidirectional"))
      (node (ref "R145") (pin "2") (pinfunction "2_2") (pintype "passive"))
    )
    (net (code "63") (name "/LVDS_DUAL_P1") (class "Default")
      (node (ref "IC27") (pin "7") (pinfunction "A1+_7") (pintype "bidirectional"))
      (node (ref "J32") (pin "5") (pinfunction "5_5") (pintype "bidirectional"))
      (node (ref "R146") (pin "2") (pinfunction "2_2") (pintype "passive"))
    )
    (net (code "64") (name "/LVDS_DUAL_P2") (class "Default")
      (node (ref "IC28") (pin "3") (pinfunction "A0+_3") (pintype "bidirectional"))
      (node (ref "J32") (pin "8") (pinfunction "8_8") (pintype "bidirectional"))
      (node (ref "R147") (pin "2") (pinfunction "2_2") (pintype "passive"))
    )
    (net (code "65") (name "/LVDS_DUAL_P3") (class "Default")
      (node (ref "IC28") (pin "7") (pinfunction "A1+_7") (pintype "bidirectional"))
      (node (ref "J32") (pin "11") (pinfunction "11_11") (pintype "bidirectional"))
      (node (ref "R148") (pin "2") (pinfunction "2_2") (pintype "passive"))
    )
    (net (code "66") (name "/LVDS_DUAL_P4") (class "Default")
      (node (ref "IC42") (pin "3") (pinfunction "A0+_3") (pintype "bidirectional"))
      (node (ref "J32") (pin "14") (pinfunction "14_14") (pintype "bidirectional"))
      (node (ref "R149") (pin "2") (pinfunction "2_2") (pintype "passive"))
    )
    (net (code "68") (name "/LVDS_JTAG_TCK_N") (class "Default")
      (node (ref "IC30") (pin "8") (pinfunction "IN4-_8") (pintype "input"))
      (node (ref "IC42") (pin "14") (pinfunction "C0-_14") (pintype "bidirectional"))
    )
    (net (code "69") (name "/LVDS_JTAG_TCK_P") (class "Default")
      (node (ref "IC30") (pin "7") (pinfunction "IN4+_7") (pintype "input"))
      (node (ref "IC42") (pin "15") (pinfunction "C0+_15") (pintype "bidirectional"))
    )
    (net (code "70") (name "/LVDS_JTAG_TDI_N") (class "Default")
      (node (ref "IC27") (pin "12") (pinfunction "C1-_12") (pintype "bidirectional"))
      (node (ref "IC30") (pin "1") (pinfunction "IN1-_1") (pintype "input"))
    )
    (net (code "71") (name "/LVDS_JTAG_TDI_P") (class "Default")
      (node (ref "IC27") (pin "13") (pinfunction "C1+_13") (pintype "bidirectional"))
      (node (ref "IC30") (pin "2") (pinfunction "IN1+_2") (pintype "input"))
    )
    (net (code "72") (name "/LVDS_JTAG_TDO_N") (class "Default")
      (node (ref "IC27") (pin "14") (pinfunction "C0-_14") (pintype "bidirectional"))
      (node (ref "IC31") (pin "8") (pinfunction "DOUT-_8") (pintype "output"))
    )
    (net (code "73") (name "/LVDS_JTAG_TDO_P") (class "Default")
      (node (ref "IC27") (pin "15") (pinfunction "C0+_15") (pintype "bidirectional"))
      (node (ref "IC31") (pin "7") (pinfunction "DOUT+_7") (pintype "output"))
    )
    (net (code "74") (name "/LVDS_JTAG_TMS_N") (class "Default")
      (node (ref "IC28") (pin "14") (pinfunction "C0-_14") (pintype "bidirectional"))
      (node (ref "IC30") (pin "5") (pinfunction "IN3-_5") (pintype "input"))
    )
    (net (code "75") (name "/LVDS_JTAG_TMS_P") (class "Default")
      (node (ref "IC28") (pin "15") (pinfunction "C0+_15") (pintype "bidirectional"))
      (node (ref "IC30") (pin "6") (pinfunction "IN3+_6") (pintype "input"))
    )
    (net (code "76") (name "/LVDS_JTAG_TRSTn_N") (class "Default")
      (node (ref "IC28") (pin "12") (pinfunction "C1-_12") (pintype "bidirectional"))
      (node (ref "IC30") (pin "4") (pinfunction "IN2-_4") (pintype "input"))
    )
    (net (code "77") (name "/LVDS_JTAG_TRSTn_P") (class "Default")
      (node (ref "IC28") (pin "13") (pinfunction "C1+_13") (pintype "bidirectional"))
      (node (ref "IC30") (pin "3") (pinfunction "IN2+_3") (pintype "input"))
    )
    (net (code "78") (name "/PROG_TCK") (class "Default")
      (node (ref "D11") (pin "3") (pinfunction "C_3") (pintype "passive"))
      (node (ref "IC16") (pin "2") (pinfunction "1B1_2") (pintype "bidirectional"))
      (node (ref "J34") (pin "6") (pinfunction "6_6") (pintype "bidirectional"))
      (node (ref "R263") (pin "1") (pinfunction "1_1") (pintype "passive"))
    )
    (net (code "79") (name "/PROG_TDI") (class "Default")
      (node (ref "D11") (pin "5") (pinfunction "C_5") (pintype "passive"))
      (node (ref "IC16") (pin "14") (pinfunction "4B1_14") (pintype "bidirectional"))
      (node (ref "J34") (pin "10") (pinfunction "10_10") (pintype "bidirectional"))
      (node (ref "R264") (pin "1") (pinfunction "1_1") (pintype "passive"))
    )
    (net (code "80") (name "/PROG_TDO") (class "Default")
      (node (ref "D11") (pin "6") (pinfunction "C_6") (pintype "passive"))
      (node (ref "IC16") (pin "11") (pinfunction "3B1_11") (pintype "bidirectional"))
      (node (ref "J34") (pin "8") (pinfunction "8_8") (pintype "bidirectional"))
    )
    (net (code "81") (name "/PROG_TMS") (class "Default")
      (node (ref "D11") (pin "1") (pinfunction "C_1") (pintype "passive"))
      (node (ref "IC16") (pin "5") (pinfunction "2B1_5") (pintype "bidirectional"))
      (node (ref "J34") (pin "4") (pinfunction "4_4") (pintype "bidirectional"))
      (node (ref "R259") (pin "1") (pinfunction "1_1") (pintype "passive"))
    )
    (net (code "82") (name "/PROG_TRST") (class "Default")
      (node (ref "D11") (pin "4") (pinfunction "C_4") (pintype "passive"))
      (node (ref "IC26") (pin "3") (pinfunction "I0_3") (pintype "input"))
      (node (ref "R265") (pin "1") (pinfunction "1_1") (pintype "passive"))
      (node (ref "R266") (pin "1") (pinfunction "1_1") (pintype "passive"))
    )
    (net (code "83") (name "/SERVMOD_3V3") (class "Default")
      (node (ref "IC16") (pin "1") (pinfunction "S_1") (pintype "input"))
      (node (ref "IC26") (pin "6") (pinfunction "S_6") (pintype "input"))
      (node (ref "IC27") (pin "9") (pinfunction "SEL_9") (pintype "input"))
      (node (ref "IC28") (pin "9") (pinfunction "SEL_9") (pintype "input"))
      (node (ref "IC30") (pin "16") (pinfunction "EN_16") (pintype "input"))
      (node (ref "IC42") (pin "9") (pinfunction "SEL_9") (pintype "input"))
      (node (ref "T13") (pin "1") (pinfunction "G_1") (pintype "passive"))
    )
    (net (code "89") (name "GND") (class "Default")
      (node (ref "C119") (pin "1") (pinfunction "1_1") (pintype "passive"))
      (node (ref "C180") (pin "1") (pinfunction "1_1") (pintype "passive"))
      (node (ref "C219") (pin "1") (pinfunction "1_1") (pintype "passive"))
      (node (ref "C221") (pin "1") (pinfunction "1_1") (pintype "passive"))
      (node (ref "C222") (pin "1") (pinfunction "1_1") (pintype "passive"))
      (node (ref "C223") (pin "1") (pinfunction "1_1") (pintype "passive"))
      (node (ref "C224") (pin "1") (pinfunction "1_1") (pintype "passive"))
      (node (ref "C226") (pin "1") (pinfunction "1_1") (pintype "passive"))
      (node (ref "C51") (pin "1") (pinfunction "1_1") (pintype "passive"))
      (node (ref "C53") (pin "1") (pinfunction "1_1") (pintype "passive"))
      (node (ref "D11") (pin "2") (pinfunction "A_2") (pintype "passive"))
      (node (ref "D8") (pin "2") (pinfunction "A_2") (pintype "passive"))
      (node (ref "IC16") (pin "8") (pinfunction "GND_8") (pintype "power_in"))
      (node (ref "IC25") (pin "1") (pinfunction "A0_1") (pintype "input"))
      (node (ref "IC25") (pin "2") (pinfunction "A1_2") (pintype "input"))
      (node (ref "IC25") (pin "3") (pinfunction "A2_3") (pintype "input"))
      (node (ref "IC25") (pin "4") (pinfunction "VSS_4") (pintype "power_in"))
      (node (ref "IC26") (pin "2") (pinfunction "GND_2") (pintype "power_in"))
      (node (ref "IC27") (pin "11") (pinfunction "GND_11") (pintype "power_in"))
      (node (ref "IC27") (pin "20") (pinfunction "GND_20") (pintype "power_in"))
      (node (ref "IC27") (pin "21") (pinfunction "EP_21") (pintype "power_in"))
      (node (ref "IC27") (pin "5") (pinfunction "GND_5") (pintype "power_in"))
      (node (ref "IC28") (pin "11") (pinfunction "GND_11") (pintype "power_in"))
      (node (ref "IC28") (pin "20") (pinfunction "GND_20") (pintype "power_in"))
      (node (ref "IC28") (pin "21") (pinfunction "EP_21") (pintype "power_in"))
      (node (ref "IC28") (pin "5") (pinfunction "GND_5") (pintype "power_in"))
      (node (ref "IC3") (pin "2") (pinfunction "VSS_2") (pintype "power_in"))
      (node (ref "IC3") (pin "4") (pinfunction "A1_4") (pintype "input"))
      (node (ref "IC3") (pin "5") (pinfunction "A0_5") (pintype "input"))
      (node (ref "IC30") (pin "12") (pinfunction "GND_12") (pintype "power_in"))
      (node (ref "IC30") (pin "9") (pinfunction "~{EN}_9") (pintype "input"))
      (node (ref "IC31") (pin "4") (pinfunction "GND_4") (pintype "power_in"))
      (node (ref "IC42") (pin "11") (pinfunction "GND_11") (pintype "power_in"))
      (node (ref "IC42") (pin "20") (pinfunction "GND_20") (pintype "power_in"))
      (node (ref "IC42") (pin "21") (pinfunction "EP_21") (pintype "power_in"))
      (node (ref "IC42") (pin "5") (pinfunction "GND_5") (pintype "power_in"))
      (node (ref "J32") (pin "1") (pinfunction "1_1") (pintype "bidirectional"))
      (node (ref "J32") (pin "10") (pinfunction "10_10") (pintype "bidirectional"))
      (node (ref "J32") (pin "13") (pinfunction "13_13") (pintype "bidirectional"))
      (node (ref "J32") (pin "16") (pinfunction "16_16") (pintype "bidirectional"))
      (node (ref "J32") (pin "19") (pinfunction "19_19") (pintype "bidirectional"))
      (node (ref "J32") (pin "22") (pinfunction "22_22") (pintype "bidirectional"))
      (node (ref "J32") (pin "25") (pinfunction "25_25") (pintype "bidirectional"))
      (node (ref "J32") (pin "4") (pinfunction "4_4") (pintype "bidirectional"))
      (node (ref "J32") (pin "7") (pinfunction "7_7") (pintype "bidirectional"))
      (node (ref "J34") (pin "1") (pinfunction "1_1") (pintype "bidirectional"))
      (node (ref "J34") (pin "11") (pinfunction "11_11") (pintype "bidirectional"))
      (node (ref "J34") (pin "3") (pinfunction "3_3") (pintype "bidirectional"))
      (node (ref "J34") (pin "5") (pinfunction "5_5") (pintype "bidirectional"))
      (node (ref "J34") (pin "7") (pinfunction "7_7") (pintype "bidirectional"))
      (node (ref "J34") (pin "9") (pinfunction "9_9") (pintype "bidirectional"))
      (node (ref "R143") (pin "2") (pinfunction "2_2") (pintype "passive"))
      (node (ref "R244") (pin "1") (pinfunction "1_1") (pintype "passive"))
      (node (ref "R255") (pin "2") (pinfunction "2_2") (pintype "passive"))
      (node (ref "R256") (pin "2") (pinfunction "2_2") (pintype "passive"))
      (node (ref "T13") (pin "2") (pinfunction "S_2") (pintype "passive"))
    )
    (net (code "90") (name "Net-(IC16-~{OE})") (class "Default")
      (node (ref "IC16") (pin "15") (pinfunction "~{OE}_15") (pintype "input"))
      (node (ref "R244") (pin "2") (pinfunction "2_2") (pintype "passive"))
    )
    (net (code "91") (name "Net-(IC27-OEn)") (class "Default")
      (node (ref "IC27") (pin "2") (pinfunction "OEn_2") (pintype "input"))
      (node (ref "R255") (pin "1") (pinfunction "1_1") (pintype "passive"))
    )
    (net (code "92") (name "Net-(IC28-OEn)") (class "Default")
      (node (ref "IC28") (pin "2") (pinfunction "OEn_2") (pintype "input"))
      (node (ref "R256") (pin "1") (pinfunction "1_1") (pintype "passive"))
    )
    (net (code "93") (name "Net-(IC42-OEn)") (class "Default")
      (node (ref "IC42") (pin "2") (pinfunction "OEn_2") (pintype "input"))
      (node (ref "R143") (pin "1") (pinfunction "1_1") (pintype "passive"))
    )
    (net (code "94") (name "Net-(J34-Pad14)") (class "Default")
      (node (ref "J34") (pin "14") (pinfunction "14_14") (pintype "bidirectional"))
      (node (ref "R266") (pin "2") (pinfunction "2_2") (pintype "passive"))
    )
    (net (code "95") (name "P3V3") (class "Default")
      (node (ref "C119") (pin "2") (pinfunction "2_2") (pintype "passive"))
      (node (ref "C180") (pin "2") (pinfunction "2_2") (pintype "passive"))
      (node (ref "C221") (pin "2") (pinfunction "2_2") (pintype "passive"))
      (node (ref "C222") (pin "2") (pinfunction "2_2") (pintype "passive"))
      (node (ref "C223") (pin "2") (pinfunction "2_2") (pintype "passive"))
      (node (ref "C224") (pin "2") (pinfunction "2_2") (pintype "passive"))
      (node (ref "C226") (pin "2") (pinfunction "2_2") (pintype "passive"))
      (node (ref "C51") (pin "2") (pinfunction "2_2") (pintype "passive"))
      (node (ref "IC16") (pin "16") (pinfunction "VCC_16") (pintype "power_in"))
      (node (ref "IC26") (pin "5") (pinfunction "VCC_5") (pintype "power_in"))
      (node (ref "IC27") (pin "1") (pinfunction "RSVD1_1") (pintype "power_in"))
      (node (ref "IC27") (pin "10") (pinfunction "RSVD2_10") (pintype "power_in"))
      (node (ref "IC27") (pin "6") (pinfunction "VDD_6") (pintype "power_in"))
      (node (ref "IC28") (pin "1") (pinfunction "RSVD1_1") (pintype "power_in"))
      (node (ref "IC28") (pin "10") (pinfunction "RSVD2_10") (pintype "power_in"))
      (node (ref "IC28") (pin "6") (pinfunction "VDD_6") (pintype "power_in"))
      (node (ref "IC30") (pin "13") (pinfunction "VCC_13") (pintype "power_in"))
      (node (ref "IC31") (pin "1") (pinfunction "VCC_1") (pintype "power_in"))
      (node (ref "IC42") (pin "1") (pinfunction "RSVD1_1") (pintype "power_in"))
      (node (ref "IC42") (pin "10") (pinfunction "RSVD2_10") (pintype "power_in"))
      (node (ref "IC42") (pin "6") (pinfunction "VDD_6") (pintype "power_in"))
      (node (ref "J34") (pin "2") (pinfunction "2_2") (pintype "bidirectional"))
      (node (ref "R259") (pin "2") (pinfunction "2_2") (pintype "passive"))
      (node (ref "R263") (pin "2") (pinfunction "2_2") (pintype "passive"))
      (node (ref "R264") (pin "2") (pinfunction "2_2") (pintype "passive"))
      (node (ref "R265") (pin "2") (pinfunction "2_2") (pintype "passive"))
      (node (ref "R58") (pin "2") (pinfunction "2_2") (pintype "passive"))
    )
    (net (code "96") (name "P3V3_MP") (class "Default")
      (node (ref "C219") (pin "2") (pinfunction "2_2") (pintype "passive"))
      (node (ref "IC25") (pin "8") (pinfunction "VCC_8") (pintype "power_in"))
      (node (ref "IC3") (pin "6") (pinfunction "VCC_6") (pintype "power_in"))
      (node (ref "J32") (pin "30") (pinfunction "30_30") (pintype "bidirectional"))
    )
    (net (code "97") (name "P12V0") (class "Default")
      (node (ref "J32") (pin "28") (pinfunction "28_28") (pintype "bidirectional"))
      (node (ref "J32") (pin "29") (pinfunction "29_29") (pintype "bidirectional"))
    )
    (net (code "98") (name "unconnected-(D8C-C-Pad4)") (class "Default")
      (node (ref "D8") (pin "4") (pinfunction "C_4") (pintype "passive"))
    )
    (net (code "99") (name "unconnected-(D8D-C-Pad5)") (class "Default")
      (node (ref "D8") (pin "5") (pinfunction "C_5") (pintype "passive+no_connect"))
    )
    (net (code "100") (name "unconnected-(D8E-C-Pad6)") (class "Default")
      (node (ref "D8") (pin "6") (pinfunction "C_6") (pintype "passive"))
    )
    (net (code "101") (name "unconnected-(IC25-NC-Pad7)") (class "Default")
      (node (ref "IC25") (pin "7") (pinfunction "NC_7") (pintype "passive+no_connect"))
    )
    (net (code "102") (name "unconnected-(IC31-NC-Pad3)") (class "Default")
      (node (ref "IC31") (pin "3") (pinfunction "NC_3") (pintype "passive"))
    )
    (net (code "103") (name "unconnected-(IC31-NC-Pad5)") (class "Default")
      (node (ref "IC31") (pin "5") (pinfunction "NC_5") (pintype "passive"))
    )
    (net (code "104") (name "unconnected-(IC31-NC-Pad6)") (class "Default")
      (node (ref "IC31") (pin "6") (pinfunction "NC_6") (pintype "passive"))
    )
    (net (code "105") (name "unconnected-(IC42-B1+-Pad17)") (class "Default")
      (node (ref "IC42") (pin "17") (pinfunction "B1+_17") (pintype "bidirectional+no_connect"))
    )
    (net (code "106") (name "unconnected-(IC42-B1--Pad16)") (class "Default")
      (node (ref "IC42") (pin "16") (pinfunction "B1-_16") (pintype "bidirectional+no_connect"))
    )
    (net (code "107") (name "unconnected-(J34-Pad12)") (class "Default")
      (node (ref "J34") (pin "12") (pinfunction "12_12") (pintype "bidirectional+no_connect"))
    )
  )
)
